# Power_Supply.net
KiCad netlist of a schematic drawn in Altium Designer
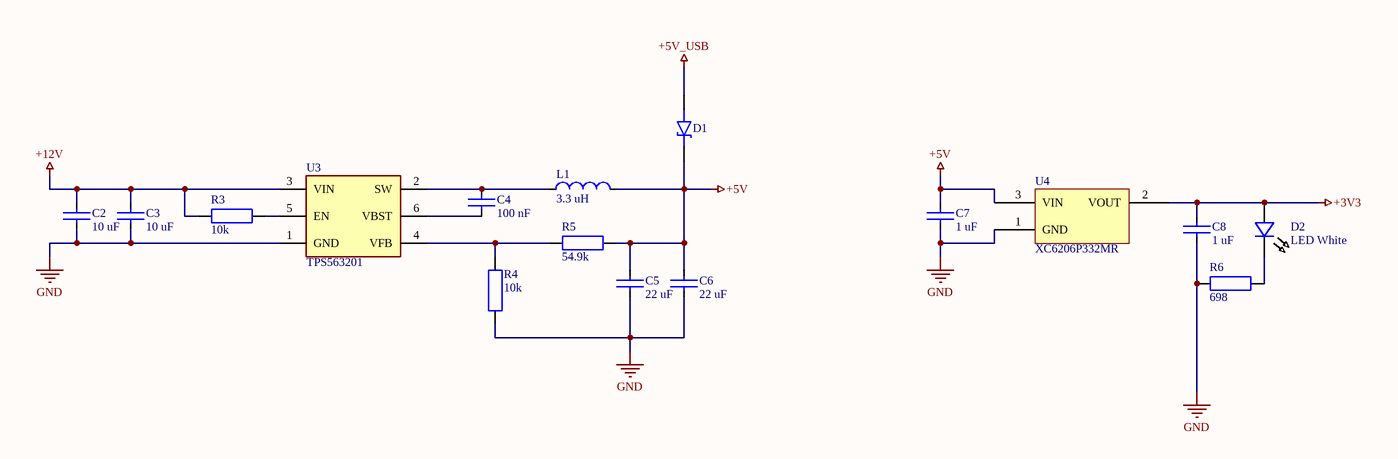
[diagram p0: Power Supply.SchDoc]

(export (version "E")
  (design (tool "Eeschema 10.0.6"))
  (components
    (comp (ref "C2")
      (value "10 uF")
      (footprint "0603 SMD CAP")
      (description "25V 10uF X5R ±20% 0603 Multilayer Ceramic Capacitors")
      (fields (field (name "PART NUMBER") "CL10A106MA8NRNC"))
      (libsource (lib "Max_lib") (part "Cap 10uf 0603"))
    )
    (comp (ref "C3")
      (value "10 uF")
      (footprint "0603 SMD CAP")
      (description "25V 10uF X5R ±20% 0603 Multilayer Ceramic Capacitors")
      (fields (field (name "PART NUMBER") "CL10A106MA8NRNC"))
      (libsource (lib "Max_lib") (part "Cap 10uf 0603"))
    )
    (comp (ref "C4")
      (value "100 nF")
      (footprint "0603 SMD CAP")
      (description "25V 100nF X7R ±10% 0603 Multilayer Ceramic Capacitors MLCC")
      (fields (field (name "PART NUMBER") "CL10B104KA8NNNC"))
      (libsource (lib "Max_lib") (part "Cap 100nF 0603"))
    )
    (comp (ref "C5")
      (value "22 uF")
      (footprint "0805 SMD Cap")
      (description "25V 22uF X5R ±20% 0805 Multilayer Ceramic Capacitors")
      (fields (field (name "PART NUMBER") "CL21A226MAYNNNE"))
      (libsource (lib "Max_lib") (part "Cap 22uF 0805"))
    )
    (comp (ref "C6")
      (value "22 uF")
      (footprint "0805 SMD Cap")
      (description "25V 22uF X5R ±20% 0805 Multilayer Ceramic Capacitors")
      (fields (field (name "PART NUMBER") "CL21A226MAYNNNE"))
      (libsource (lib "Max_lib") (part "Cap 22uF 0805"))
    )
    (comp (ref "C7")
      (value "1 uF")
      (footprint "0603 SMD CAP")
      (description "25V 1uF X5R ±10% 0603 Multilayer Ceramic Capacitors MLCC")
      (fields (field (name "PART NUMBER") "CC0603KRX5R8BB105"))
      (libsource (lib "Max_lib") (part "Cap 1u 0603"))
    )
    (comp (ref "C8")
      (value "1 uF")
      (footprint "0603 SMD CAP")
      (description "25V 1uF X5R ±10% 0603 Multilayer Ceramic Capacitors MLCC")
      (fields (field (name "PART NUMBER") "CC0603KRX5R8BB105"))
      (libsource (lib "Max_lib") (part "Cap 1u 0603"))
    )
    (comp (ref "D1")
      (value "Diode Shottky SOD-323")
      (footprint "SOD-323")
      (description "20V 450mV@1A 1A SOD-323 Schottky Barrier Diodes")
      (fields (field (name "PART NUMBER") "B5817WS"))
      (libsource (lib "Max_lib") (part "Diode Shottky SOD-323"))
    )
    (comp (ref "D2")
      (value "LED White")
      (footprint "0603 SMD LED")
      (description "5mA Yellow -40℃~+85℃ White light 120° 100mW 0603 Light Emitting Diodes (LED) ROHS")
      (fields (field (name "PART NUMBER") "SZYY0603W"))
      (libsource (lib "Max_lib") (part "LED White 0603"))
    )
    (comp (ref "L1")
      (value "3.3 uH")
      (footprint "1210 Inductor SMD")
      (description "1.55A 3.3uH ±30% 1.9A 100mΩ 1210 Inductors (SMD) ROHS")
      (fields (field (name "PART NUMBER") "LQH32PN3R3NNCL"))
      (libsource (lib "Max_lib") (part "Ind 3.3mH 1210"))
    )
    (comp (ref "R3")
      (value "10k")
      (footprint "0603 SMD Res")
      (description "Resistor 10k 0603 1%")
      (fields (field (name "PART NUMBER") "RC0603FR-0710KL"))
      (libsource (lib "Max_lib") (part "Resistor 10k 0603 1%"))
    )
    (comp (ref "R4")
      (value "10k")
      (footprint "0603 SMD Res")
      (description "Resistor 10k 0603 1%")
      (fields (field (name "PART NUMBER") "RC0603FR-0710KL"))
      (libsource (lib "Max_lib") (part "Resistor 10k 0603 1%"))
    )
    (comp (ref "R5")
      (value "54.9k")
      (footprint "0603 SMD Res")
      (description "100mW Thick Film Resistors 75V ±100ppm/℃ ±1% -55℃~+155℃ 54.9kΩ 0603")
      (fields (field (name "PART NUMBER") "RC0603FR-0754K9L"))
      (libsource (lib "Max_lib") (part "Resistor 54.9k 0603 1%"))
    )
    (comp (ref "R6")
      (value "698")
      (footprint "0603 SMD Res")
      (description "100mW Thick Film Resistors 75V ±100ppm/℃ ±1% -55℃~+155℃ 698Ω 0603 Chip Resistor")
      (fields (field (name "PART NUMBER") "AC0603FR-07698RL"))
      (libsource (lib "Max_lib") (part "Resistor 698 0603 1%"))
    )
    (comp (ref "U3")
      (value "TPS563201")
      (footprint "SOT23-6L")
      (description "Step-down type -40℃~+125℃@(TJ) 1 Step-down Adjustable 0.768V~7V 3A 4.5V~17V 580kHz SOT-23-THIN-6")
      (fields (field (name "PART NUMBER") "TPS563201DDCR"))
      (libsource (lib "Max_lib") (part "DC-DC Buck Converter TPS563201"))
    )
    (comp (ref "U4")
      (value "XC6206P332MR")
      (footprint "SOT23-3")
      (description "40dB@(1kHz) 100mA 240mV@(50mA) Fixed 3.3V~3.3V Positive 1 8V SOT-23 Linear Voltage Regulators")
      (libsource (lib "Max_lib") (part "LDO 3V3 SOT-23-3"))
    )
  )
  (nets
    (net (code "1") (name "+3V3") (class "Default")
      (node (ref "C8") (pin "2") (pinfunction "2_2") (pintype "passive"))
      (node (ref "D2") (pin "1") (pinfunction "1_1") (pintype "passive"))
      (node (ref "U4") (pin "2") (pinfunction "VOUT_2") (pintype "passive"))
    )
    (net (code "2") (name "+5V") (class "Default")
      (node (ref "C5") (pin "2") (pinfunction "2_2") (pintype "passive"))
      (node (ref "C6") (pin "2") (pinfunction "2_2") (pintype "passive"))
      (node (ref "C7") (pin "2") (pinfunction "2_2") (pintype "passive"))
      (node (ref "D1") (pin "2") (pinfunction "2_2") (pintype "passive"))
      (node (ref "L1") (pin "2") (pinfunction "2_2") (pintype "passive"))
      (node (ref "R5") (pin "1") (pinfunction "1_1") (pintype "passive"))
      (node (ref "U4") (pin "3") (pinfunction "VIN_3") (pintype "passive"))
    )
    (net (code "3") (name "+5V_USB") (class "Default")
      (node (ref "D1") (pin "1") (pinfunction "1_1") (pintype "passive"))
    )
    (net (code "4") (name "+12V") (class "Default")
      (node (ref "C2") (pin "2") (pinfunction "2_2") (pintype "passive"))
      (node (ref "C3") (pin "2") (pinfunction "2_2") (pintype "passive"))
      (node (ref "R3") (pin "2") (pinfunction "2_2") (pintype "passive"))
      (node (ref "U3") (pin "3") (pinfunction "VIN_3") (pintype "passive"))
    )
    (net (code "5") (name "GND") (class "Default")
      (node (ref "C2") (pin "1") (pinfunction "1_1") (pintype "passive"))
      (node (ref "C3") (pin "1") (pinfunction "1_1") (pintype "passive"))
      (node (ref "C5") (pin "1") (pinfunction "1_1") (pintype "passive"))
      (node (ref "C6") (pin "1") (pinfunction "1_1") (pintype "passive"))
      (node (ref "C7") (pin "1") (pinfunction "1_1") (pintype "passive"))
      (node (ref "C8") (pin "1") (pinfunction "1_1") (pintype "passive"))
      (node (ref "R4") (pin "1") (pinfunction "1_1") (pintype "passive"))
      (node (ref "R6") (pin "2") (pinfunction "2_2") (pintype "passive"))
      (node (ref "U3") (pin "1") (pinfunction "GND_1") (pintype "passive"))
      (node (ref "U4") (pin "1") (pinfunction "GND_1") (pintype "passive"))
    )
    (net (code "6") (name "Net-(D2-Pad2)") (class "Default")
      (node (ref "D2") (pin "2") (pinfunction "2_2") (pintype "passive"))
      (node (ref "R6") (pin "1") (pinfunction "1_1") (pintype "passive"))
    )
    (net (code "7") (name "Net-(U3-EN)") (class "Default")
      (node (ref "R3") (pin "1") (pinfunction "1_1") (pintype "passive"))
      (node (ref "U3") (pin "5") (pinfunction "EN_5") (pintype "passive"))
    )
    (net (code "8") (name "Net-(U3-SW)") (class "Default")
      (node (ref "C4") (pin "2") (pinfunction "2_2") (pintype "passive"))
      (node (ref "L1") (pin "1") (pinfunction "1_1") (pintype "passive"))
      (node (ref "U3") (pin "2") (pinfunction "SW_2") (pintype "passive"))
    )
    (net (code "9") (name "Net-(U3-VBST)") (class "Default")
      (node (ref "C4") (pin "1") (pinfunction "1_1") (pintype "passive"))
      (node (ref "U3") (pin "6") (pinfunction "VBST_6") (pintype "passive"))
    )
    (net (code "10") (name "Net-(U3-VFB)") (class "Default")
      (node (ref "R4") (pin "2") (pinfunction "2_2") (pintype "passive"))
      (node (ref "R5") (pin "2") (pinfunction "2_2") (pintype "passive"))
      (node (ref "U3") (pin "4") (pinfunction "VFB_4") (pintype "passive"))
    )
  )
)
